# Motor4.net
KiCad netlist of a schematic drawn in Altium Designer
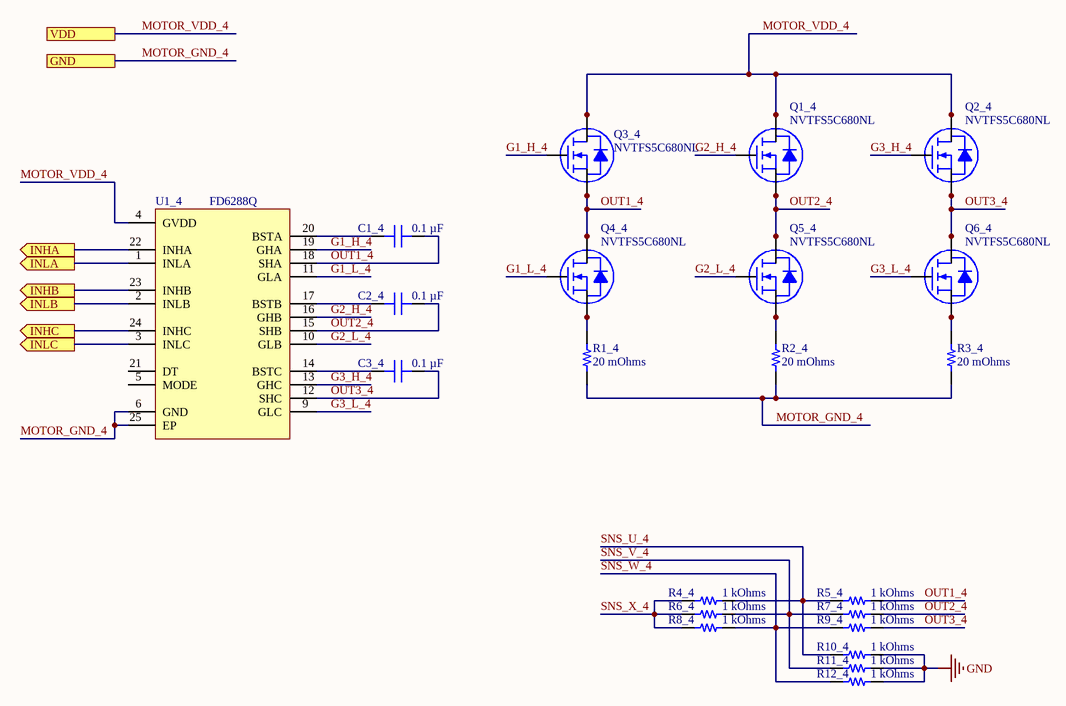
[diagram p0: Motor4.SchDoc]

(export (version "E")
  (design (tool "Eeschema 10.0.6"))
  (components
    (comp (ref "C1_4")
      (value "0.1 µF")
      (footprint "CAP 0402_1005")
      (description "CAP CER 0.1UF 16V X7R 0402")
      (fields (field (name "PART NUMBER") "C0402C104K4RACAUTO") (field (name "MANUFACTURER") "KEMET"))
      (libsource (lib "Celestial Altium Library - altium_library") (part "Capacitor"))
    )
    (comp (ref "C2_4")
      (value "0.1 µF")
      (footprint "CAP 0402_1005")
      (description "CAP CER 0.1UF 16V X7R 0402")
      (fields (field (name "PART NUMBER") "C0402C104K4RACAUTO") (field (name "MANUFACTURER") "KEMET"))
      (libsource (lib "Celestial Altium Library - altium_library") (part "Capacitor"))
    )
    (comp (ref "C3_4")
      (value "0.1 µF")
      (footprint "CAP 0402_1005")
      (description "CAP CER 0.1UF 16V X7R 0402")
      (fields (field (name "PART NUMBER") "C0402C104K4RACAUTO") (field (name "MANUFACTURER") "KEMET"))
      (libsource (lib "Celestial Altium Library - altium_library") (part "Capacitor"))
    )
    (comp (ref "Q1_4")
      (value "NVTFS5C680NL")
      (footprint "NVTFS015N04CTAG")
      (description "N-FET")
      (libsource (lib "IC") (part "NVTFS5C680NL"))
    )
    (comp (ref "Q2_4")
      (value "NVTFS5C680NL")
      (footprint "NVTFS015N04CTAG")
      (description "N-FET")
      (libsource (lib "IC") (part "NVTFS5C680NL"))
    )
    (comp (ref "Q3_4")
      (value "NVTFS5C680NL")
      (footprint "NVTFS015N04CTAG")
      (description "N-FET")
      (libsource (lib "IC") (part "NVTFS5C680NL"))
    )
    (comp (ref "Q4_4")
      (value "NVTFS5C680NL")
      (footprint "NVTFS015N04CTAG")
      (description "N-FET")
      (libsource (lib "IC") (part "NVTFS5C680NL"))
    )
    (comp (ref "Q5_4")
      (value "NVTFS5C680NL")
      (footprint "NVTFS015N04CTAG")
      (description "N-FET")
      (libsource (lib "IC") (part "NVTFS5C680NL"))
    )
    (comp (ref "Q6_4")
      (value "NVTFS5C680NL")
      (footprint "NVTFS015N04CTAG")
      (description "N-FET")
      (libsource (lib "IC") (part "NVTFS5C680NL"))
    )
    (comp (ref "R1_4")
      (value "20 mOhms")
      (footprint "STACKPOLE CSR0805")
      (description "RES 0.02 OHM 1% 1/3W 0603")
      (fields
        (field (name "PART NUMBER") "ERJ-3BWFR020V")
        (field (name "MANUFACTURER") "Panasonic Electronic Components")
      )
      (libsource (lib "Celestial Altium Library - altium_library") (part "Resistor"))
    )
    (comp (ref "R2_4")
      (value "20 mOhms")
      (footprint "STACKPOLE CSR0805")
      (description "RES 0.02 OHM 1% 1/3W 0603")
      (fields
        (field (name "PART NUMBER") "ERJ-3BWFR020V")
        (field (name "MANUFACTURER") "Panasonic Electronic Components")
      )
      (libsource (lib "Celestial Altium Library - altium_library") (part "Resistor"))
    )
    (comp (ref "R3_4")
      (value "20 mOhms")
      (footprint "STACKPOLE CSR0805")
      (description "RES 0.02 OHM 1% 1/3W 0603")
      (fields
        (field (name "PART NUMBER") "ERJ-3BWFR020V")
        (field (name "MANUFACTURER") "Panasonic Electronic Components")
      )
      (libsource (lib "Celestial Altium Library - altium_library") (part "Resistor"))
    )
    (comp (ref "R4_4")
      (value "1 kOhms")
      (footprint "RES 0402_1005")
      (description "RES 14.3K OHM 1% 1/10W 0402")
      (fields
        (field (name "PART NUMBER") "RK73H1ETTP1432F")
        (field (name "MANUFACTURER") "KOA Speer Electronics, Inc.")
      )
      (libsource (lib "Celestial Altium Library - altium_library") (part "Resistor"))
    )
    (comp (ref "R5_4")
      (value "1 kOhms")
      (footprint "RES 0402_1005")
      (description "RES 14.3K OHM 1% 1/10W 0402")
      (fields
        (field (name "PART NUMBER") "RK73H1ETTP1432F")
        (field (name "MANUFACTURER") "KOA Speer Electronics, Inc.")
      )
      (libsource (lib "Celestial Altium Library - altium_library") (part "Resistor"))
    )
    (comp (ref "R6_4")
      (value "1 kOhms")
      (footprint "RES 0402_1005")
      (description "RES 14.3K OHM 1% 1/10W 0402")
      (fields
        (field (name "PART NUMBER") "RK73H1ETTP1432F")
        (field (name "MANUFACTURER") "KOA Speer Electronics, Inc.")
      )
      (libsource (lib "Celestial Altium Library - altium_library") (part "Resistor"))
    )
    (comp (ref "R7_4")
      (value "1 kOhms")
      (footprint "RES 0402_1005")
      (description "RES 14.3K OHM 1% 1/10W 0402")
      (fields
        (field (name "PART NUMBER") "RK73H1ETTP1432F")
        (field (name "MANUFACTURER") "KOA Speer Electronics, Inc.")
      )
      (libsource (lib "Celestial Altium Library - altium_library") (part "Resistor"))
    )
    (comp (ref "R8_4")
      (value "1 kOhms")
      (footprint "RES 0402_1005")
      (description "RES 14.3K OHM 1% 1/10W 0402")
      (fields
        (field (name "PART NUMBER") "RK73H1ETTP1432F")
        (field (name "MANUFACTURER") "KOA Speer Electronics, Inc.")
      )
      (libsource (lib "Celestial Altium Library - altium_library") (part "Resistor"))
    )
    (comp (ref "R9_4")
      (value "1 kOhms")
      (footprint "RES 0402_1005")
      (description "RES 14.3K OHM 1% 1/10W 0402")
      (fields
        (field (name "PART NUMBER") "RK73H1ETTP1432F")
        (field (name "MANUFACTURER") "KOA Speer Electronics, Inc.")
      )
      (libsource (lib "Celestial Altium Library - altium_library") (part "Resistor"))
    )
    (comp (ref "R10_4")
      (value "1 kOhms")
      (footprint "RES 0402_1005")
      (description "RES 14.3K OHM 1% 1/10W 0402")
      (fields
        (field (name "PART NUMBER") "RK73H1ETTP1432F")
        (field (name "MANUFACTURER") "KOA Speer Electronics, Inc.")
      )
      (libsource (lib "Celestial Altium Library - altium_library") (part "Resistor"))
    )
    (comp (ref "R11_4")
      (value "1 kOhms")
      (footprint "RES 0402_1005")
      (description "RES 14.3K OHM 1% 1/10W 0402")
      (fields
        (field (name "PART NUMBER") "RK73H1ETTP1432F")
        (field (name "MANUFACTURER") "KOA Speer Electronics, Inc.")
      )
      (libsource (lib "Celestial Altium Library - altium_library") (part "Resistor"))
    )
    (comp (ref "R12_4")
      (value "1 kOhms")
      (footprint "RES 0402_1005")
      (description "RES 14.3K OHM 1% 1/10W 0402")
      (fields
        (field (name "PART NUMBER") "RK73H1ETTP1432F")
        (field (name "MANUFACTURER") "KOA Speer Electronics, Inc.")
      )
      (libsource (lib "Celestial Altium Library - altium_library") (part "Resistor"))
    )
    (comp (ref "U1_4")
      (value "FD6288Q")
      (footprint "QFN50P400X400X100-25N")
      (description "3 Phase Gate Driver 1.5-2.2A")
      (fields (field (name "MF") "Texas Instruments") (field (name "MP") "UCC27282DRCR"))
      (libsource (lib "IC") (part "FD6288Q"))
    )
  )
  (nets
    (net (code "1") (name "/G1_H_4") (class "Default")
      (node (ref "Q3_4") (pin "4") (pinfunction "G_4") (pintype "passive"))
      (node (ref "U1_4") (pin "19") (pinfunction "GHA_19") (pintype "passive"))
    )
    (net (code "2") (name "/G1_L_4") (class "Default")
      (node (ref "Q4_4") (pin "4") (pinfunction "G_4") (pintype "passive"))
      (node (ref "U1_4") (pin "11") (pinfunction "GLA_11") (pintype "passive"))
    )
    (net (code "3") (name "/G2_H_4") (class "Default")
      (node (ref "Q1_4") (pin "4") (pinfunction "G_4") (pintype "passive"))
      (node (ref "U1_4") (pin "16") (pinfunction "GHB_16") (pintype "passive"))
    )
    (net (code "4") (name "/G2_L_4") (class "Default")
      (node (ref "Q5_4") (pin "4") (pinfunction "G_4") (pintype "passive"))
      (node (ref "U1_4") (pin "10") (pinfunction "GLB_10") (pintype "passive"))
    )
    (net (code "5") (name "/G3_H_4") (class "Default")
      (node (ref "Q2_4") (pin "4") (pinfunction "G_4") (pintype "passive"))
      (node (ref "U1_4") (pin "13") (pinfunction "GHC_13") (pintype "passive"))
    )
    (net (code "6") (name "/G3_L_4") (class "Default")
      (node (ref "Q6_4") (pin "4") (pinfunction "G_4") (pintype "passive"))
      (node (ref "U1_4") (pin "9") (pinfunction "GLC_9") (pintype "passive"))
    )
    (net (code "7") (name "/INHA") (class "Default")
      (node (ref "U1_4") (pin "22") (pinfunction "INHA_22") (pintype "passive"))
    )
    (net (code "8") (name "/INHB") (class "Default")
      (node (ref "U1_4") (pin "23") (pinfunction "INHB_23") (pintype "passive"))
    )
    (net (code "9") (name "/INHC") (class "Default")
      (node (ref "U1_4") (pin "24") (pinfunction "INHC_24") (pintype "passive"))
    )
    (net (code "10") (name "/INLA") (class "Default")
      (node (ref "U1_4") (pin "1") (pinfunction "INLA_1") (pintype "passive"))
    )
    (net (code "11") (name "/INLB") (class "Default")
      (node (ref "U1_4") (pin "2") (pinfunction "INLB_2") (pintype "passive"))
    )
    (net (code "12") (name "/INLC") (class "Default")
      (node (ref "U1_4") (pin "3") (pinfunction "INLC_3") (pintype "passive"))
    )
    (net (code "13") (name "/MOTOR_VDD_4") (class "Default")
      (node (ref "Q1_4") (pin "5") (pinfunction "D_5") (pintype "passive"))
      (node (ref "Q1_4") (pin "6") (pinfunction "D_6") (pintype "passive"))
      (node (ref "Q1_4") (pin "7") (pinfunction "D_7") (pintype "passive"))
      (node (ref "Q1_4") (pin "8") (pinfunction "D_8") (pintype "passive"))
      (node (ref "Q2_4") (pin "5") (pinfunction "D_5") (pintype "passive"))
      (node (ref "Q2_4") (pin "6") (pinfunction "D_6") (pintype "passive"))
      (node (ref "Q2_4") (pin "7") (pinfunction "D_7") (pintype "passive"))
      (node (ref "Q2_4") (pin "8") (pinfunction "D_8") (pintype "passive"))
      (node (ref "Q3_4") (pin "5") (pinfunction "D_5") (pintype "passive"))
      (node (ref "Q3_4") (pin "6") (pinfunction "D_6") (pintype "passive"))
      (node (ref "Q3_4") (pin "7") (pinfunction "D_7") (pintype "passive"))
      (node (ref "Q3_4") (pin "8") (pinfunction "D_8") (pintype "passive"))
      (node (ref "U1_4") (pin "4") (pinfunction "GVDD_4") (pintype "passive"))
    )
    (net (code "14") (name "/OUT1_4") (class "Default")
      (node (ref "C1_4") (pin "2") (pinfunction "2_2") (pintype "passive"))
      (node (ref "Q3_4") (pin "1") (pinfunction "S_1") (pintype "passive"))
      (node (ref "Q3_4") (pin "2") (pinfunction "S_2") (pintype "passive"))
      (node (ref "Q3_4") (pin "3") (pinfunction "S_3") (pintype "passive"))
      (node (ref "Q4_4") (pin "5") (pinfunction "D_5") (pintype "passive"))
      (node (ref "Q4_4") (pin "6") (pinfunction "D_6") (pintype "passive"))
      (node (ref "Q4_4") (pin "7") (pinfunction "D_7") (pintype "passive"))
      (node (ref "Q4_4") (pin "8") (pinfunction "D_8") (pintype "passive"))
      (node (ref "R5_4") (pin "2") (pinfunction "2_2") (pintype "passive"))
      (node (ref "U1_4") (pin "18") (pinfunction "SHA_18") (pintype "passive"))
    )
    (net (code "15") (name "/OUT2_4") (class "Default")
      (node (ref "C2_4") (pin "2") (pinfunction "2_2") (pintype "passive"))
      (node (ref "Q1_4") (pin "1") (pinfunction "S_1") (pintype "passive"))
      (node (ref "Q1_4") (pin "2") (pinfunction "S_2") (pintype "passive"))
      (node (ref "Q1_4") (pin "3") (pinfunction "S_3") (pintype "passive"))
      (node (ref "Q5_4") (pin "5") (pinfunction "D_5") (pintype "passive"))
      (node (ref "Q5_4") (pin "6") (pinfunction "D_6") (pintype "passive"))
      (node (ref "Q5_4") (pin "7") (pinfunction "D_7") (pintype "passive"))
      (node (ref "Q5_4") (pin "8") (pinfunction "D_8") (pintype "passive"))
      (node (ref "R7_4") (pin "2") (pinfunction "2_2") (pintype "passive"))
      (node (ref "U1_4") (pin "15") (pinfunction "SHB_15") (pintype "passive"))
    )
    (net (code "16") (name "/OUT3_4") (class "Default")
      (node (ref "C3_4") (pin "2") (pinfunction "2_2") (pintype "passive"))
      (node (ref "Q2_4") (pin "1") (pinfunction "S_1") (pintype "passive"))
      (node (ref "Q2_4") (pin "2") (pinfunction "S_2") (pintype "passive"))
      (node (ref "Q2_4") (pin "3") (pinfunction "S_3") (pintype "passive"))
      (node (ref "Q6_4") (pin "5") (pinfunction "D_5") (pintype "passive"))
      (node (ref "Q6_4") (pin "6") (pinfunction "D_6") (pintype "passive"))
      (node (ref "Q6_4") (pin "7") (pinfunction "D_7") (pintype "passive"))
      (node (ref "Q6_4") (pin "8") (pinfunction "D_8") (pintype "passive"))
      (node (ref "R9_4") (pin "2") (pinfunction "2_2") (pintype "passive"))
      (node (ref "U1_4") (pin "12") (pinfunction "SHC_12") (pintype "passive"))
    )
    (net (code "17") (name "/SNS_U_4") (class "Default")
      (node (ref "R10_4") (pin "2") (pinfunction "2_2") (pintype "passive"))
      (node (ref "R4_4") (pin "2") (pinfunction "2_2") (pintype "passive"))
      (node (ref "R5_4") (pin "1") (pinfunction "1_1") (pintype "passive"))
    )
    (net (code "18") (name "/SNS_V_4") (class "Default")
      (node (ref "R11_4") (pin "2") (pinfunction "2_2") (pintype "passive"))
      (node (ref "R6_4") (pin "2") (pinfunction "2_2") (pintype "passive"))
      (node (ref "R7_4") (pin "1") (pinfunction "1_1") (pintype "passive"))
    )
    (net (code "19") (name "/SNS_W_4") (class "Default")
      (node (ref "R12_4") (pin "2") (pinfunction "2_2") (pintype "passive"))
      (node (ref "R8_4") (pin "2") (pinfunction "2_2") (pintype "passive"))
      (node (ref "R9_4") (pin "1") (pinfunction "1_1") (pintype "passive"))
    )
    (net (code "20") (name "/SNS_X_4") (class "Default")
      (node (ref "R4_4") (pin "1") (pinfunction "1_1") (pintype "passive"))
      (node (ref "R6_4") (pin "1") (pinfunction "1_1") (pintype "passive"))
      (node (ref "R8_4") (pin "1") (pinfunction "1_1") (pintype "passive"))
    )
    (net (code "21") (name "GND") (class "Default")
      (node (ref "R10_4") (pin "1") (pinfunction "1_1") (pintype "passive"))
      (node (ref "R11_4") (pin "1") (pinfunction "1_1") (pintype "passive"))
      (node (ref "R12_4") (pin "1") (pinfunction "1_1") (pintype "passive"))
      (node (ref "R1_4") (pin "1") (pinfunction "1_1") (pintype "passive"))
      (node (ref "R2_4") (pin "1") (pinfunction "1_1") (pintype "passive"))
      (node (ref "R3_4") (pin "1") (pinfunction "1_1") (pintype "passive"))
      (node (ref "U1_4") (pin "25") (pinfunction "EP_25") (pintype "passive"))
      (node (ref "U1_4") (pin "6") (pinfunction "GND_6") (pintype "passive"))
    )
    (net (code "22") (name "Net-(Q4_4-S-Pad1)") (class "Default")
      (node (ref "Q4_4") (pin "1") (pinfunction "S_1") (pintype "passive"))
      (node (ref "Q4_4") (pin "2") (pinfunction "S_2") (pintype "passive"))
      (node (ref "Q4_4") (pin "3") (pinfunction "S_3") (pintype "passive"))
      (node (ref "R1_4") (pin "2") (pinfunction "2_2") (pintype "passive"))
    )
    (net (code "23") (name "Net-(Q5_4-S-Pad1)") (class "Default")
      (node (ref "Q5_4") (pin "1") (pinfunction "S_1") (pintype "passive"))
      (node (ref "Q5_4") (pin "2") (pinfunction "S_2") (pintype "passive"))
      (node (ref "Q5_4") (pin "3") (pinfunction "S_3") (pintype "passive"))
      (node (ref "R2_4") (pin "2") (pinfunction "2_2") (pintype "passive"))
    )
    (net (code "24") (name "Net-(Q6_4-S-Pad1)") (class "Default")
      (node (ref "Q6_4") (pin "1") (pinfunction "S_1") (pintype "passive"))
      (node (ref "Q6_4") (pin "2") (pinfunction "S_2") (pintype "passive"))
      (node (ref "Q6_4") (pin "3") (pinfunction "S_3") (pintype "passive"))
      (node (ref "R3_4") (pin "2") (pinfunction "2_2") (pintype "passive"))
    )
    (net (code "25") (name "Net-(U1_4-BSTA)") (class "Default")
      (node (ref "C1_4") (pin "1") (pinfunction "1_1") (pintype "passive"))
      (node (ref "U1_4") (pin "20") (pinfunction "BSTA_20") (pintype "passive"))
    )
    (net (code "26") (name "Net-(U1_4-BSTB)") (class "Default")
      (node (ref "C2_4") (pin "1") (pinfunction "1_1") (pintype "passive"))
      (node (ref "U1_4") (pin "17") (pinfunction "BSTB_17") (pintype "passive"))
    )
    (net (code "27") (name "Net-(U1_4-BSTC)") (class "Default")
      (node (ref "C3_4") (pin "1") (pinfunction "1_1") (pintype "passive"))
      (node (ref "U1_4") (pin "14") (pinfunction "BSTC_14") (pintype "passive"))
    )
    (net (code "28") (name "unconnected-(U1_4-DT-Pad21)") (class "Default")
      (node (ref "U1_4") (pin "21") (pinfunction "DT_21") (pintype "passive"))
    )
    (net (code "29") (name "unconnected-(U1_4-MODE-Pad5)") (class "Default")
      (node (ref "U1_4") (pin "5") (pinfunction "MODE_5") (pintype "passive"))
    )
  )
)
